# 1-Schematic_UC2DC-Seg7.net
KiCad netlist of a schematic drawn in EasyEDA
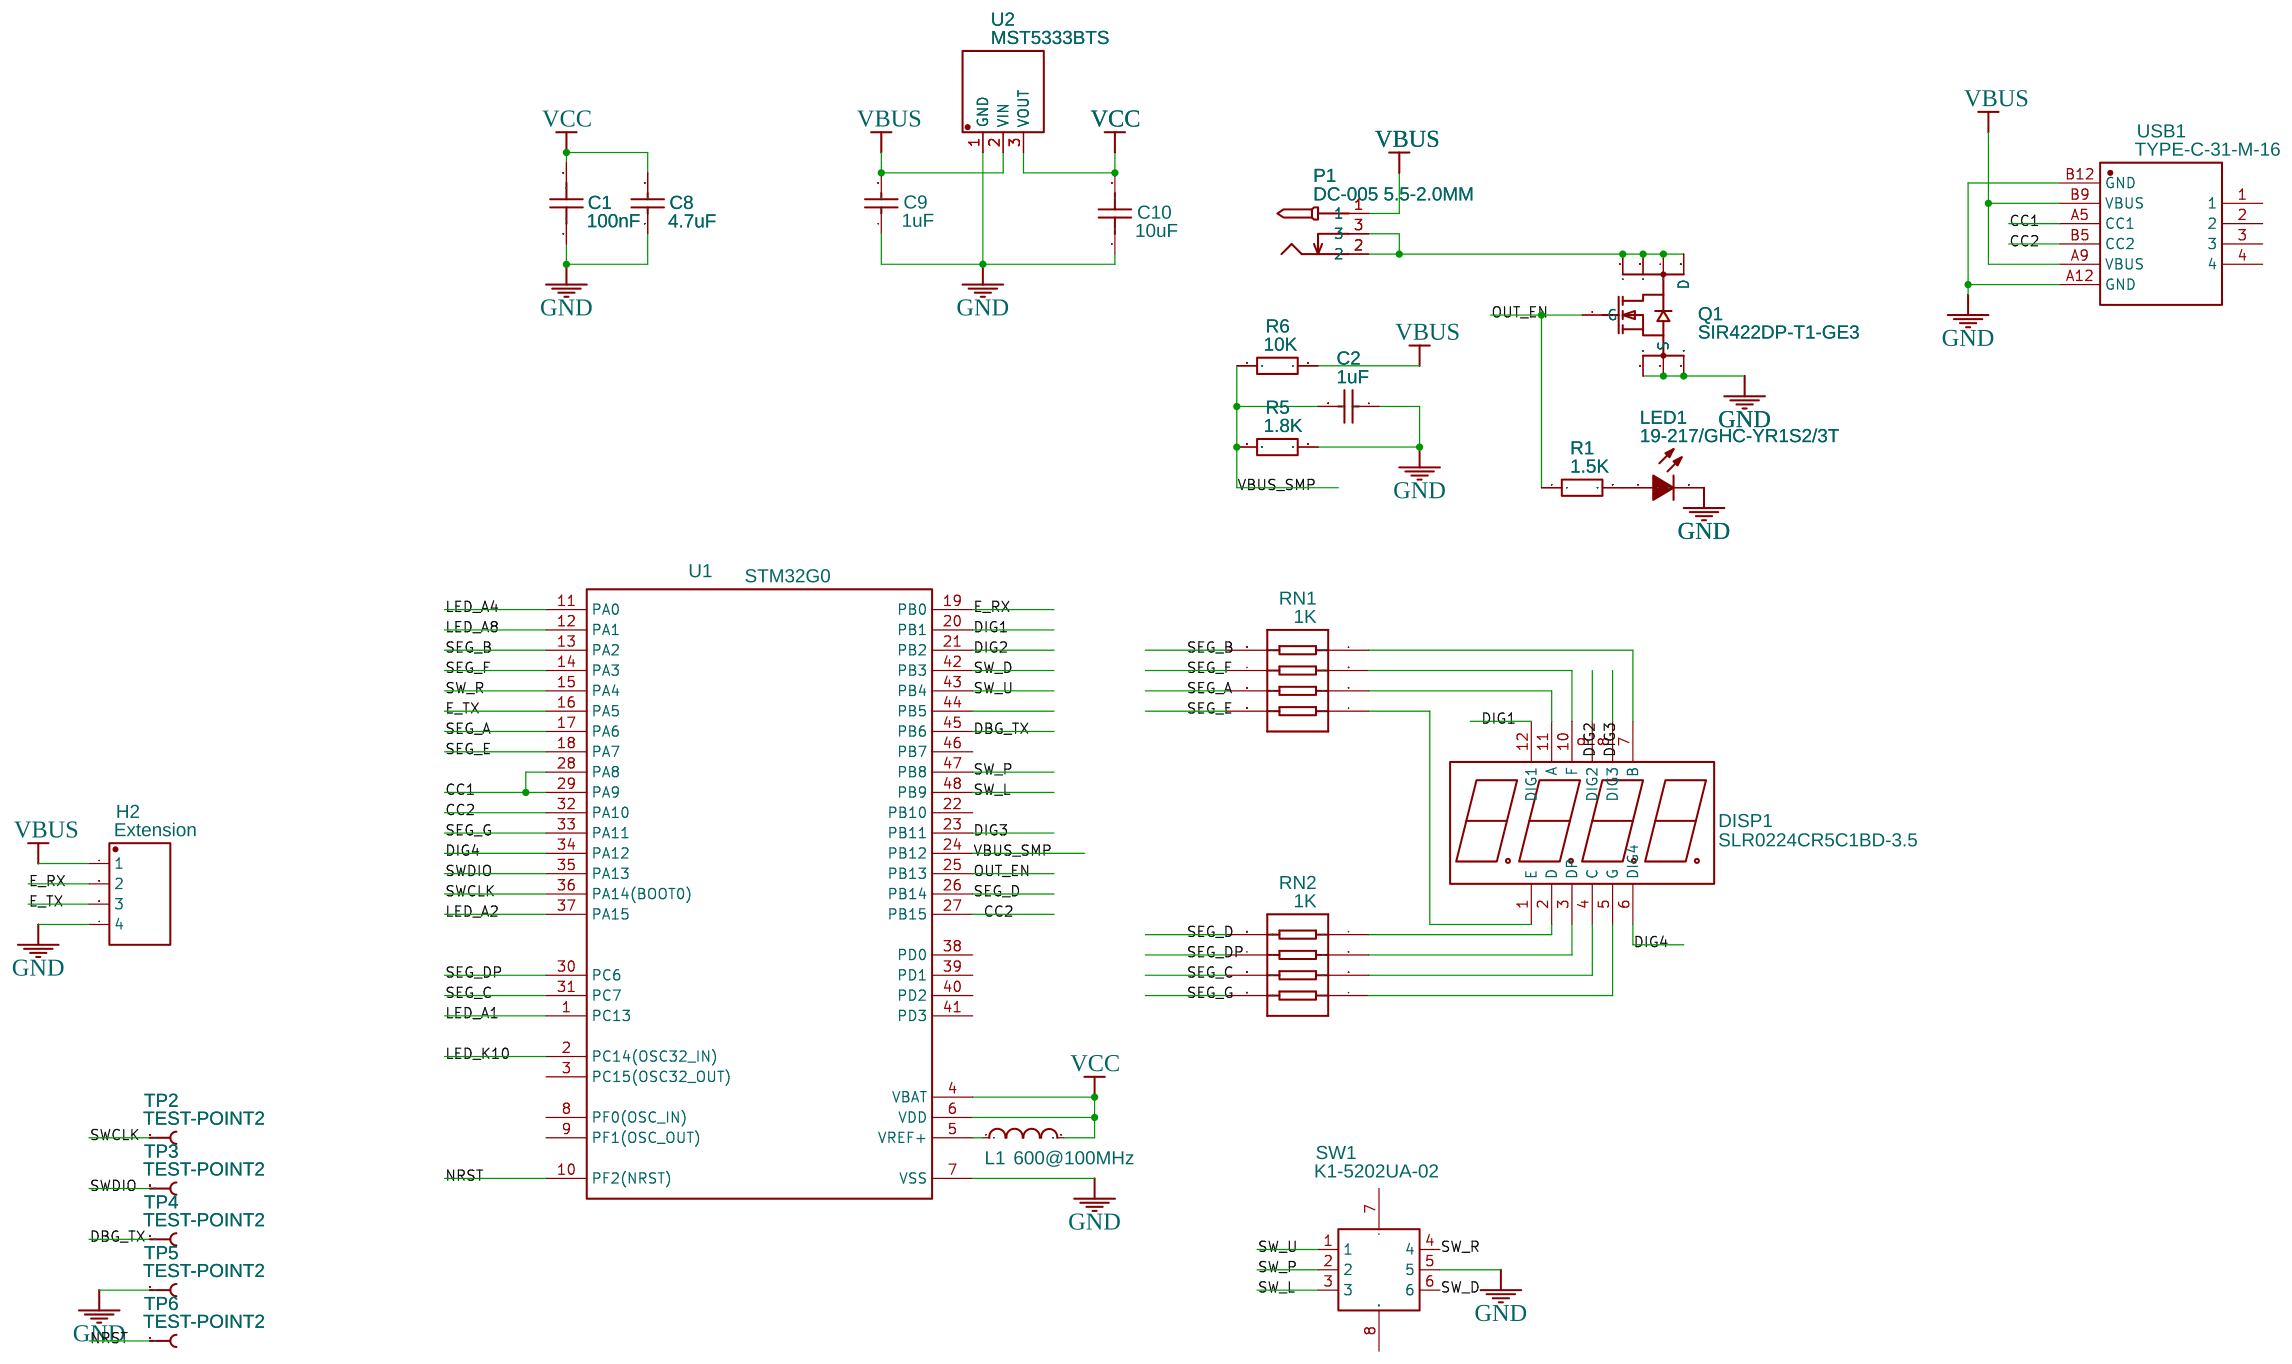
[diagram p0: schematic sheet]

(export (version "E")
  (design (tool "Eeschema 10.0.6"))
  (components
    (comp (ref "C1")
      (value "100nF")
      (fields
        (field (name "BOM_Manufacturer Part") "CC0603KRX7R9BB104")
        (field (name "BOM_Supplier Part") "C14663")
      )
      (libsource (lib "") (part "CC0603KRX7R9BB104"))
    )
    (comp (ref "C2")
      (value "1uF")
      (fields
        (field (name "BOM_Manufacturer Part") "CL10A105KB8NNNC")
        (field (name "BOM_Supplier Part") "C15849")
      )
      (libsource (lib "") (part "CL10A105KB8NNNC"))
    )
    (comp (ref "C8")
      (value "4.7uF")
      (fields
        (field (name "BOM_Manufacturer Part") "CL10A475KO8NNNC")
        (field (name "BOM_Supplier Part") "C19666")
      )
      (libsource (lib "") (part "CL10A475KO8NNNC"))
    )
    (comp (ref "C9")
      (value "1uF")
      (fields
        (field (name "BOM_Manufacturer Part") "CL10A105KB8NNNC")
        (field (name "BOM_Supplier Part") "C15849")
      )
      (libsource (lib "") (part "CL10A105KB8NNNC_1"))
    )
    (comp (ref "C10")
      (value "10uF")
      (fields
        (field (name "BOM_Manufacturer Part") "CL10A106KP8NNNC")
        (field (name "BOM_Supplier Part") "C19702")
      )
      (libsource (lib "") (part "CL10A106KP8NNNC"))
    )
    (comp (ref "DISP1")
      (value "SLR0224CR5C1BD-3.5")
      (fields (field (name "BOM_Supplier Part") "C225970"))
      (libsource (lib "") (part "SLR0224CR5C1BD-3.5"))
    )
    (comp (ref "H2")
      (value "Extension")
      (fields
        (field (name "BOM_Manufacturer Part") "210S-1*4P L=11.6MMGold-plated black")
        (field (name "BOM_Supplier Part") "C124378")
      )
      (libsource (lib "") (part "Unknown_-525_190"))
    )
    (comp (ref "L1")
      (value "600@100MHz")
      (fields
        (field (name "BOM_Manufacturer Part") "GZ1608D181TF")
        (field (name "BOM_Supplier Part") "C15909")
      )
      (libsource (lib "") (part "GZ1608D181TF"))
    )
    (comp (ref "LED1")
      (value "19-217/GHC-YR1S2/3T")
      (fields (field (name "BOM_Supplier Part") "C72043"))
      (libsource (lib "") (part "19-217/GHC-YR1S2/3T"))
    )
    (comp (ref "P1")
      (value "DC-005 5.5-2.0MM")
      (fields (field (name "BOM_Supplier Part") "C16214"))
      (libsource (lib "") (part "Unknown_65_-135"))
    )
    (comp (ref "Q1")
      (value "SIR422DP-T1-GE3")
      (fields (field (name "BOM_Supplier Part") "C21104"))
      (libsource (lib "") (part "SIR422DP-T1-GE3"))
    )
    (comp (ref "R1")
      (value "1.5K")
      (fields
        (field (name "BOM_Manufacturer Part") "0402WGF1501TCE")
        (field (name "BOM_Supplier Part") "C25867")
      )
      (libsource (lib "") (part "0402WGF1501TCE"))
    )
    (comp (ref "R5")
      (value "1.8K")
      (fields
        (field (name "BOM_Manufacturer Part") "0402WGF1801TCE")
        (field (name "BOM_Supplier Part") "C25871")
      )
      (libsource (lib "") (part "0402WGF1801TCE"))
    )
    (comp (ref "R6")
      (value "10K")
      (fields
        (field (name "BOM_Manufacturer Part") "0402WGF1002TCE")
        (field (name "BOM_Supplier Part") "C25744")
      )
      (libsource (lib "") (part "0402WGF1002TCE"))
    )
    (comp (ref "RN1")
      (value "1K")
      (fields
        (field (name "BOM_Manufacturer Part") "4D02WGJ0102TCE")
        (field (name "BOM_Supplier Part") "C25726")
      )
      (libsource (lib "") (part "4D02WGJ0102TCE"))
    )
    (comp (ref "RN2")
      (value "1K")
      (fields
        (field (name "BOM_Manufacturer Part") "4D02WGJ0102TCE")
        (field (name "BOM_Supplier Part") "C25726")
      )
      (libsource (lib "") (part "4D02WGJ0102TCE"))
    )
    (comp (ref "SW1")
      (value "K1-5202UA-02")
      (fields (field (name "BOM_Supplier Part") "C145900"))
      (libsource (lib "") (part "Unknown_90_375"))
    )
    (comp (ref "TP2")
      (value "TEST-POINT2")
      (fields (field (name "BOM_Manufacturer Part") "?"))
      (libsource (lib "") (part "Unknown_-510_310"))
    )
    (comp (ref "TP3")
      (value "TEST-POINT2")
      (fields (field (name "BOM_Manufacturer Part") "?"))
      (libsource (lib "") (part "Unknown_-510_335"))
    )
    (comp (ref "TP4")
      (value "TEST-POINT2")
      (fields (field (name "BOM_Manufacturer Part") "?"))
      (libsource (lib "") (part "Unknown_-510_360"))
    )
    (comp (ref "TP5")
      (value "TEST-POINT2")
      (fields (field (name "BOM_Manufacturer Part") "?"))
      (libsource (lib "") (part "Unknown_-510_385"))
    )
    (comp (ref "TP6")
      (value "TEST-POINT2")
      (fields (field (name "BOM_Manufacturer Part") "?"))
      (libsource (lib "") (part "Unknown_-510_410"))
    )
    (comp (ref "U1") (value "STM32G0") (libsource (lib "") (part "Unknown_-210_190")))
    (comp (ref "U2")
      (value "MST5333BTS")
      (fields (field (name "BOM_Supplier Part") "C324582"))
      (libsource (lib "") (part "Unknown_-95_-195"))
    )
    (comp (ref "USB1")
      (value "TYPE-C-31-M-16")
      (fields (field (name "BOM_Supplier Part") "C283541"))
      (libsource (lib "") (part "Unknown_475_-130"))
    )
  )
  (nets
    (net (code "1") (name "/CC1") (class "Default")
      (node (ref "U1") (pin "28") (pinfunction "PA8_28") (pintype "unspecified"))
      (node (ref "U1") (pin "29") (pinfunction "PA9_29") (pintype "unspecified"))
      (node (ref "USB1") (pin "A5") (pinfunction "CC1_A5") (pintype "unspecified"))
    )
    (net (code "2") (name "/CC2") (class "Default")
      (node (ref "U1") (pin "27") (pinfunction "PB15_27") (pintype "unspecified"))
      (node (ref "U1") (pin "32") (pinfunction "PA10_32") (pintype "unspecified"))
      (node (ref "USB1") (pin "B5") (pinfunction "CC2_B5") (pintype "unspecified"))
    )
    (net (code "3") (name "/DBG_TX") (class "Default")
      (node (ref "TP4") (pin "P$1") (pinfunction "1_P$1") (pintype "unspecified"))
      (node (ref "U1") (pin "45") (pinfunction "PB6_45") (pintype "unspecified"))
    )
    (net (code "4") (name "/DIG1") (class "Default")
      (node (ref "DISP1") (pin "12") (pinfunction "DIG1_12") (pintype "unspecified"))
      (node (ref "U1") (pin "20") (pinfunction "PB1_20") (pintype "unspecified"))
    )
    (net (code "5") (name "/DIG2") (class "Default")
      (node (ref "DISP1") (pin "9") (pinfunction "DIG2_9") (pintype "unspecified"))
      (node (ref "U1") (pin "21") (pinfunction "PB2_21") (pintype "unspecified"))
    )
    (net (code "6") (name "/DIG3") (class "Default")
      (node (ref "DISP1") (pin "8") (pinfunction "DIG3_8") (pintype "unspecified"))
      (node (ref "U1") (pin "23") (pinfunction "PB11_23") (pintype "unspecified"))
    )
    (net (code "7") (name "/DIG4") (class "Default")
      (node (ref "DISP1") (pin "6") (pinfunction "DIG4_6") (pintype "unspecified"))
      (node (ref "U1") (pin "34") (pinfunction "PA12_34") (pintype "unspecified"))
    )
    (net (code "8") (name "/E_RX") (class "Default")
      (node (ref "H2") (pin "2") (pinfunction "2_2") (pintype "unspecified"))
      (node (ref "U1") (pin "19") (pinfunction "PB0_19") (pintype "unspecified"))
    )
    (net (code "9") (name "/E_TX") (class "Default")
      (node (ref "H2") (pin "3") (pinfunction "3_3") (pintype "unspecified"))
      (node (ref "U1") (pin "16") (pinfunction "PA5_16") (pintype "unspecified"))
    )
    (net (code "10") (name "/LED_A1") (class "Default")
      (node (ref "U1") (pin "1") (pinfunction "PC13_1") (pintype "unspecified"))
    )
    (net (code "11") (name "/LED_A2") (class "Default")
      (node (ref "U1") (pin "37") (pinfunction "PA15_37") (pintype "unspecified"))
    )
    (net (code "12") (name "/LED_A4") (class "Default")
      (node (ref "U1") (pin "11") (pinfunction "PA0_11") (pintype "unspecified"))
    )
    (net (code "13") (name "/LED_A8") (class "Default")
      (node (ref "U1") (pin "12") (pinfunction "PA1_12") (pintype "unspecified"))
    )
    (net (code "14") (name "/LED_K10") (class "Default")
      (node (ref "U1") (pin "2") (pinfunction "PC14(OSC32_IN)_2") (pintype "unspecified"))
    )
    (net (code "15") (name "/NRST") (class "Default")
      (node (ref "TP6") (pin "P$1") (pinfunction "1_P$1") (pintype "unspecified"))
      (node (ref "U1") (pin "10") (pinfunction "PF2(NRST)_10") (pintype "unspecified"))
    )
    (net (code "16") (name "/OUT_EN") (class "Default")
      (node (ref "Q1") (pin "4") (pinfunction "G_4") (pintype "unspecified"))
      (node (ref "R1") (pin "1") (pinfunction "1_1") (pintype "input"))
      (node (ref "U1") (pin "25") (pinfunction "PB13_25") (pintype "unspecified"))
    )
    (net (code "17") (name "/SEG_A") (class "Default")
      (node (ref "RN1") (pin "6") (pinfunction "6_6") (pintype "input"))
      (node (ref "U1") (pin "17") (pinfunction "PA6_17") (pintype "unspecified"))
    )
    (net (code "18") (name "/SEG_B") (class "Default")
      (node (ref "RN1") (pin "8") (pinfunction "8_8") (pintype "input"))
      (node (ref "U1") (pin "13") (pinfunction "PA2_13") (pintype "unspecified"))
    )
    (net (code "19") (name "/SEG_C") (class "Default")
      (node (ref "RN2") (pin "6") (pinfunction "6_6") (pintype "input"))
      (node (ref "U1") (pin "31") (pinfunction "PC7_31") (pintype "unspecified"))
    )
    (net (code "20") (name "/SEG_D") (class "Default")
      (node (ref "RN2") (pin "8") (pinfunction "8_8") (pintype "input"))
      (node (ref "U1") (pin "26") (pinfunction "PB14_26") (pintype "unspecified"))
    )
    (net (code "21") (name "/SEG_DP") (class "Default")
      (node (ref "RN2") (pin "7") (pinfunction "7_7") (pintype "input"))
      (node (ref "U1") (pin "30") (pinfunction "PC6_30") (pintype "unspecified"))
    )
    (net (code "22") (name "/SEG_E") (class "Default")
      (node (ref "RN1") (pin "5") (pinfunction "5_5") (pintype "input"))
      (node (ref "U1") (pin "18") (pinfunction "PA7_18") (pintype "unspecified"))
    )
    (net (code "23") (name "/SEG_F") (class "Default")
      (node (ref "RN1") (pin "7") (pinfunction "7_7") (pintype "input"))
      (node (ref "U1") (pin "14") (pinfunction "PA3_14") (pintype "unspecified"))
    )
    (net (code "24") (name "/SEG_G") (class "Default")
      (node (ref "RN2") (pin "5") (pinfunction "5_5") (pintype "input"))
      (node (ref "U1") (pin "33") (pinfunction "PA11_33") (pintype "unspecified"))
    )
    (net (code "25") (name "/SWCLK") (class "Default")
      (node (ref "TP2") (pin "P$1") (pinfunction "1_P$1") (pintype "unspecified"))
      (node (ref "U1") (pin "36") (pinfunction "PA14(BOOT0)_36") (pintype "unspecified"))
    )
    (net (code "26") (name "/SWDIO") (class "Default")
      (node (ref "TP3") (pin "P$1") (pinfunction "1_P$1") (pintype "unspecified"))
      (node (ref "U1") (pin "35") (pinfunction "PA13_35") (pintype "unspecified"))
    )
    (net (code "27") (name "/SW_D") (class "Default")
      (node (ref "SW1") (pin "6") (pinfunction "6_6") (pintype "unspecified"))
      (node (ref "U1") (pin "42") (pinfunction "PB3_42") (pintype "unspecified"))
    )
    (net (code "28") (name "/SW_L") (class "Default")
      (node (ref "SW1") (pin "3") (pinfunction "3_3") (pintype "unspecified"))
      (node (ref "U1") (pin "48") (pinfunction "PB9_48") (pintype "unspecified"))
    )
    (net (code "29") (name "/SW_P") (class "Default")
      (node (ref "SW1") (pin "2") (pinfunction "2_2") (pintype "unspecified"))
      (node (ref "U1") (pin "47") (pinfunction "PB8_47") (pintype "unspecified"))
    )
    (net (code "30") (name "/SW_R") (class "Default")
      (node (ref "SW1") (pin "4") (pinfunction "4_4") (pintype "unspecified"))
      (node (ref "U1") (pin "15") (pinfunction "PA4_15") (pintype "unspecified"))
    )
    (net (code "31") (name "/SW_U") (class "Default")
      (node (ref "SW1") (pin "1") (pinfunction "1_1") (pintype "unspecified"))
      (node (ref "U1") (pin "43") (pinfunction "PB4_43") (pintype "unspecified"))
    )
    (net (code "32") (name "/VBUS_SMP") (class "Default")
      (node (ref "C2") (pin "2") (pinfunction "2_2") (pintype "input"))
      (node (ref "R5") (pin "1") (pinfunction "1_1") (pintype "input"))
      (node (ref "R6") (pin "1") (pinfunction "1_1") (pintype "input"))
      (node (ref "U1") (pin "24") (pinfunction "PB12_24") (pintype "unspecified"))
    )
    (net (code "33") (name "GND") (class "Default")
      (node (ref "C1") (pin "1") (pinfunction "1_1") (pintype "unspecified"))
      (node (ref "C10") (pin "1") (pinfunction "1_1") (pintype "unspecified"))
      (node (ref "C2") (pin "1") (pinfunction "1_1") (pintype "input"))
      (node (ref "C8") (pin "1") (pinfunction "1_1") (pintype "input"))
      (node (ref "C9") (pin "1") (pinfunction "1_1") (pintype "input"))
      (node (ref "H2") (pin "4") (pinfunction "4_4") (pintype "unspecified"))
      (node (ref "LED1") (pin "2") (pinfunction "C_2") (pintype "input"))
      (node (ref "Q1") (pin "1") (pinfunction "S_1") (pintype "unspecified"))
      (node (ref "Q1") (pin "2") (pinfunction "S_2") (pintype "unspecified"))
      (node (ref "Q1") (pin "3") (pinfunction "S_3") (pintype "unspecified"))
      (node (ref "R5") (pin "2") (pinfunction "2_2") (pintype "input"))
      (node (ref "SW1") (pin "5") (pinfunction "5_5") (pintype "unspecified"))
      (node (ref "TP5") (pin "P$1") (pinfunction "1_P$1") (pintype "unspecified"))
      (node (ref "U1") (pin "7") (pinfunction "VSS_7") (pintype "unspecified"))
      (node (ref "U2") (pin "1") (pinfunction "GND_1") (pintype "unspecified"))
      (node (ref "USB1") (pin "A12") (pinfunction "GND_A12") (pintype "unspecified"))
      (node (ref "USB1") (pin "B12") (pinfunction "GND_B12") (pintype "unspecified"))
    )
    (net (code "34") (name "Net-(DISP1-A)") (class "Default")
      (node (ref "DISP1") (pin "11") (pinfunction "A_11") (pintype "unspecified"))
      (node (ref "RN1") (pin "3") (pinfunction "3_3") (pintype "input"))
    )
    (net (code "35") (name "Net-(DISP1-B)") (class "Default")
      (node (ref "DISP1") (pin "7") (pinfunction "B_7") (pintype "unspecified"))
      (node (ref "RN1") (pin "1") (pinfunction "1_1") (pintype "input"))
    )
    (net (code "36") (name "Net-(DISP1-C)") (class "Default")
      (node (ref "DISP1") (pin "4") (pinfunction "C_4") (pintype "unspecified"))
      (node (ref "RN2") (pin "3") (pinfunction "3_3") (pintype "input"))
    )
    (net (code "37") (name "Net-(DISP1-D)") (class "Default")
      (node (ref "DISP1") (pin "2") (pinfunction "D_2") (pintype "unspecified"))
      (node (ref "RN2") (pin "1") (pinfunction "1_1") (pintype "input"))
    )
    (net (code "38") (name "Net-(DISP1-DP)") (class "Default")
      (node (ref "DISP1") (pin "3") (pinfunction "DP_3") (pintype "unspecified"))
      (node (ref "RN2") (pin "2") (pinfunction "2_2") (pintype "input"))
    )
    (net (code "39") (name "Net-(DISP1-E)") (class "Default")
      (node (ref "DISP1") (pin "1") (pinfunction "E_1") (pintype "unspecified"))
      (node (ref "RN1") (pin "4") (pinfunction "4_4") (pintype "input"))
    )
    (net (code "40") (name "Net-(DISP1-F)") (class "Default")
      (node (ref "DISP1") (pin "10") (pinfunction "F_10") (pintype "unspecified"))
      (node (ref "RN1") (pin "2") (pinfunction "2_2") (pintype "input"))
    )
    (net (code "41") (name "Net-(DISP1-G)") (class "Default")
      (node (ref "DISP1") (pin "5") (pinfunction "G_5") (pintype "unspecified"))
      (node (ref "RN2") (pin "4") (pinfunction "4_4") (pintype "input"))
    )
    (net (code "42") (name "Net-(LED1-A)") (class "Default")
      (node (ref "LED1") (pin "1") (pinfunction "A_1") (pintype "input"))
      (node (ref "R1") (pin "2") (pinfunction "2_2") (pintype "input"))
    )
    (net (code "43") (name "Net-(P1-Pad2)") (class "Default")
      (node (ref "P1") (pin "2") (pinfunction "2_2") (pintype "unspecified"))
      (node (ref "P1") (pin "3") (pinfunction "3_3") (pintype "unspecified"))
      (node (ref "Q1") (pin "5") (pinfunction "D_5") (pintype "unspecified"))
      (node (ref "Q1") (pin "6") (pinfunction "D_6") (pintype "unspecified"))
      (node (ref "Q1") (pin "7") (pinfunction "D_7") (pintype "unspecified"))
      (node (ref "Q1") (pin "8") (pinfunction "D_8") (pintype "unspecified"))
    )
    (net (code "44") (name "Net-(U1-VREF+)") (class "Default")
      (node (ref "L1") (pin "1") (pinfunction "1_1") (pintype "unspecified"))
      (node (ref "U1") (pin "5") (pinfunction "VREF+_5") (pintype "unspecified"))
    )
    (net (code "45") (name "VBUS") (class "Default")
      (node (ref "C9") (pin "2") (pinfunction "2_2") (pintype "input"))
      (node (ref "H2") (pin "1") (pinfunction "1_1") (pintype "unspecified"))
      (node (ref "P1") (pin "1") (pinfunction "1_1") (pintype "unspecified"))
      (node (ref "R6") (pin "2") (pinfunction "2_2") (pintype "input"))
      (node (ref "U2") (pin "2") (pinfunction "VIN_2") (pintype "unspecified"))
      (node (ref "USB1") (pin "A9") (pinfunction "VBUS_A9") (pintype "unspecified"))
      (node (ref "USB1") (pin "B9") (pinfunction "VBUS_B9") (pintype "unspecified"))
    )
    (net (code "46") (name "VCC") (class "Default")
      (node (ref "C1") (pin "2") (pinfunction "2_2") (pintype "unspecified"))
      (node (ref "C10") (pin "2") (pinfunction "2_2") (pintype "unspecified"))
      (node (ref "C8") (pin "2") (pinfunction "2_2") (pintype "input"))
      (node (ref "L1") (pin "2") (pinfunction "2_2") (pintype "unspecified"))
      (node (ref "U1") (pin "4") (pinfunction "VBAT_4") (pintype "unspecified"))
      (node (ref "U1") (pin "6") (pinfunction "VDD_6") (pintype "unspecified"))
      (node (ref "U2") (pin "3") (pinfunction "VOUT_3") (pintype "unspecified"))
    )
    (net (code "47") (name "unconnected-(SW1-Pad7)") (class "Default")
      (node (ref "SW1") (pin "7") (pinfunction "7_7") (pintype "unspecified"))
    )
    (net (code "48") (name "unconnected-(SW1-Pad8)") (class "Default")
      (node (ref "SW1") (pin "8") (pinfunction "8_8") (pintype "unspecified"))
    )
    (net (code "49") (name "unconnected-(U1-PB5-Pad44)") (class "Default")
      (node (ref "U1") (pin "44") (pinfunction "PB5_44") (pintype "unspecified"))
    )
    (net (code "50") (name "unconnected-(U1-PB7-Pad46)") (class "Default")
      (node (ref "U1") (pin "46") (pinfunction "PB7_46") (pintype "unspecified"))
    )
    (net (code "51") (name "unconnected-(U1-PB10-Pad22)") (class "Default")
      (node (ref "U1") (pin "22") (pinfunction "PB10_22") (pintype "unspecified"))
    )
    (net (code "52") (name "unconnected-(U1-PC15(OSC32_OUT)-Pad3)") (class "Default")
      (node (ref "U1") (pin "3") (pinfunction "PC15(OSC32_OUT)_3") (pintype "unspecified"))
    )
    (net (code "53") (name "unconnected-(U1-PD0-Pad38)") (class "Default")
      (node (ref "U1") (pin "38") (pinfunction "PD0_38") (pintype "unspecified"))
    )
    (net (code "54") (name "unconnected-(U1-PD1-Pad39)") (class "Default")
      (node (ref "U1") (pin "39") (pinfunction "PD1_39") (pintype "unspecified"))
    )
    (net (code "55") (name "unconnected-(U1-PD2-Pad40)") (class "Default")
      (node (ref "U1") (pin "40") (pinfunction "PD2_40") (pintype "unspecified"))
    )
    (net (code "56") (name "unconnected-(U1-PD3-Pad41)") (class "Default")
      (node (ref "U1") (pin "41") (pinfunction "PD3_41") (pintype "unspecified"))
    )
    (net (code "57") (name "unconnected-(U1-PF0(OSC_IN)-Pad8)") (class "Default")
      (node (ref "U1") (pin "8") (pinfunction "PF0(OSC_IN)_8") (pintype "unspecified"))
    )
    (net (code "58") (name "unconnected-(U1-PF1(OSC_OUT)-Pad9)") (class "Default")
      (node (ref "U1") (pin "9") (pinfunction "PF1(OSC_OUT)_9") (pintype "unspecified"))
    )
    (net (code "59") (name "unconnected-(USB1-Pad1)") (class "Default")
      (node (ref "USB1") (pin "1") (pinfunction "1_1") (pintype "unspecified"))
    )
    (net (code "60") (name "unconnected-(USB1-Pad2)") (class "Default")
      (node (ref "USB1") (pin "2") (pinfunction "2_2") (pintype "unspecified"))
    )
    (net (code "61") (name "unconnected-(USB1-Pad3)") (class "Default")
      (node (ref "USB1") (pin "3") (pinfunction "3_3") (pintype "unspecified"))
    )
    (net (code "62") (name "unconnected-(USB1-Pad4)") (class "Default")
      (node (ref "USB1") (pin "4") (pinfunction "4_4") (pintype "unspecified"))
    )
  )
)
